# RMP_MACRO_MODULE.net
KiCad netlist of a schematic drawn in Altium Designer
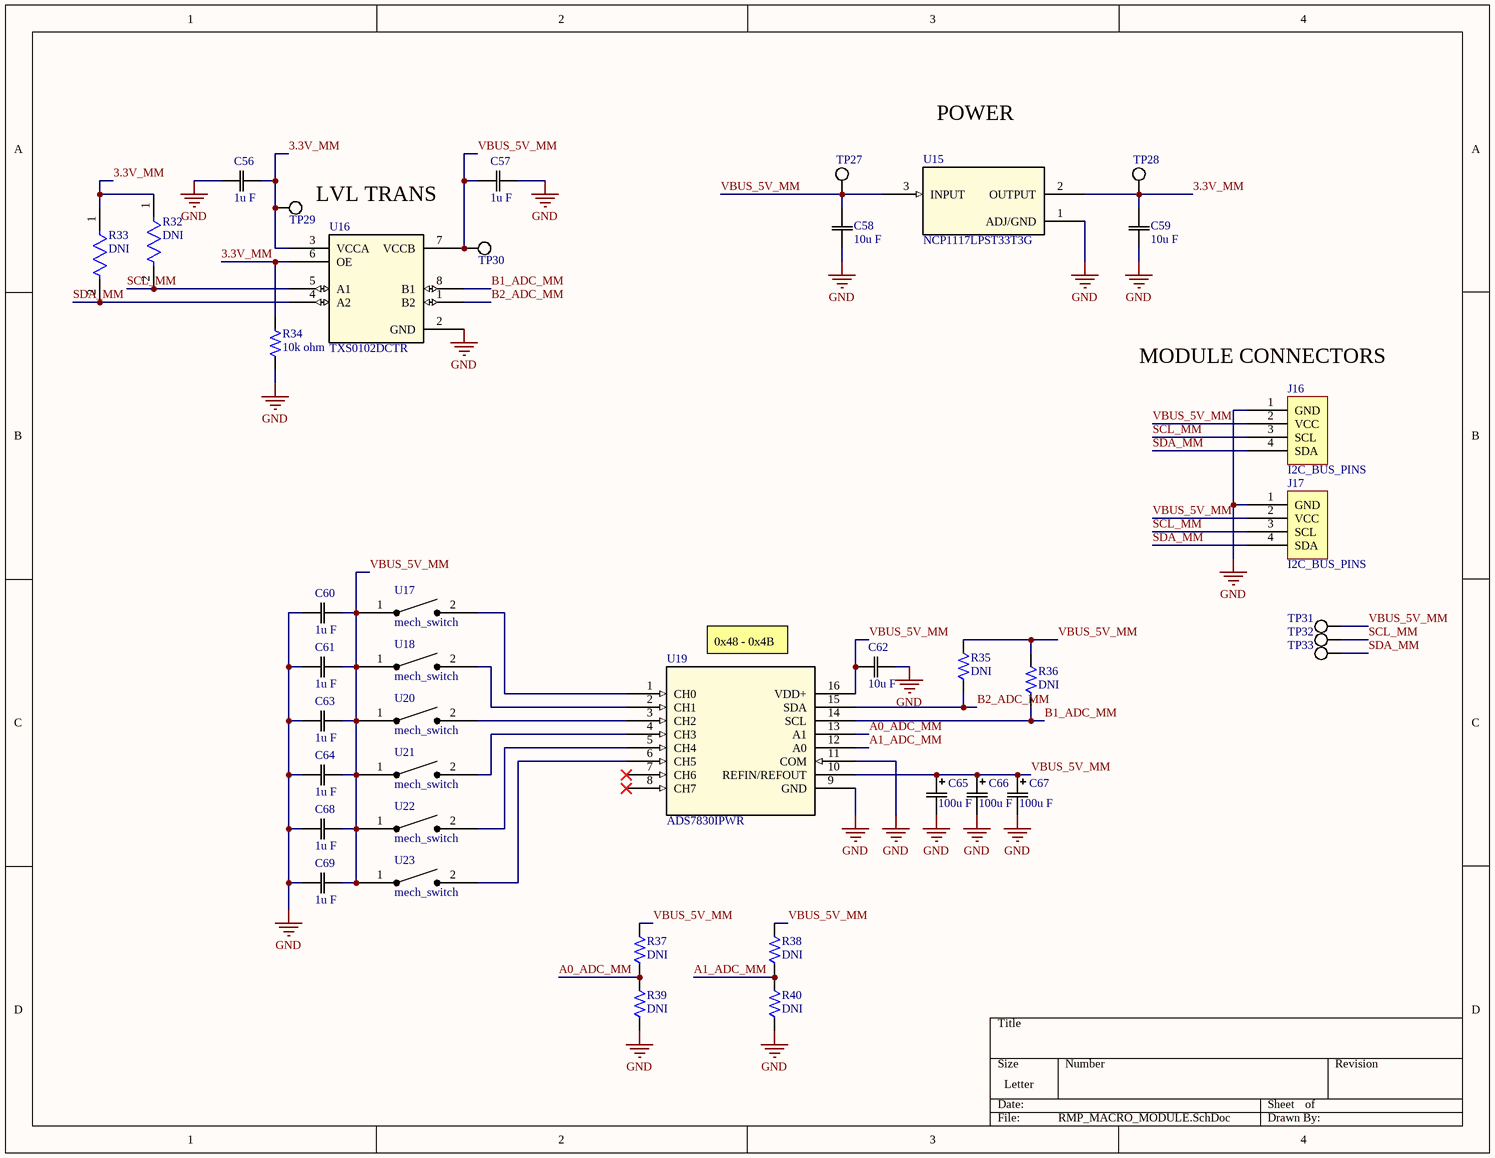
[diagram p0: RMP_MACRO_MODULE.SchDoc]

(export (version "E")
  (design (tool "Eeschema 10.0.6"))
  (components
    (comp (ref "C56")
      (value "1u F")
      (footprint "CAP_CL21B105KAFNNNE_SAM-M")
      (description "1 µF ±10% 25V Ceramic Capacitor X7R 0805 (2012 Metric)")
      (fields (field (name "Comment") "CL21B105KAFNNNE"))
      (libsource (lib "Schlib1") (part "CAP_CL21B105KAFNNNE"))
    )
    (comp (ref "C57")
      (value "1u F")
      (footprint "CAP_CL21B105KAFNNNE_SAM-M")
      (description "1 µF ±10% 25V Ceramic Capacitor X7R 0805 (2012 Metric)")
      (fields (field (name "Comment") "CL21B105KAFNNNE"))
      (libsource (lib "Schlib1") (part "CAP_CL21B105KAFNNNE"))
    )
    (comp (ref "C58")
      (value "10u F")
      (footprint "G-21_MUR-M")
      (description "10 µF ±10% 16V Ceramic Capacitor X5R 0805 (2012 Metric)")
      (fields (field (name "Comment") "GRM21BR61C106KE15K"))
      (libsource (lib "Schlib1") (part "CAP_GRM21BR61C106KE15K"))
    )
    (comp (ref "C59")
      (value "10u F")
      (footprint "G-21_MUR-M")
      (description "10 µF ±10% 16V Ceramic Capacitor X5R 0805 (2012 Metric)")
      (fields (field (name "Comment") "GRM21BR61C106KE15K"))
      (libsource (lib "Schlib1") (part "CAP_GRM21BR61C106KE15K"))
    )
    (comp (ref "C60")
      (value "1u F")
      (footprint "CAP_CL21B105KAFNNNE_SAM-M")
      (description "1 µF ±10% 25V Ceramic Capacitor X7R 0805 (2012 Metric)")
      (fields (field (name "Comment") "CL21B105KAFNNNE"))
      (libsource (lib "Schlib1") (part "CAP_CL21B105KAFNNNE"))
    )
    (comp (ref "C61")
      (value "1u F")
      (footprint "CAP_CL21B105KAFNNNE_SAM-M")
      (description "1 µF ±10% 25V Ceramic Capacitor X7R 0805 (2012 Metric)")
      (fields (field (name "Comment") "CL21B105KAFNNNE"))
      (libsource (lib "Schlib1") (part "CAP_CL21B105KAFNNNE"))
    )
    (comp (ref "C62")
      (value "10u F")
      (footprint "G-21_MUR-M")
      (description "10 µF ±10% 16V Ceramic Capacitor X5R 0805 (2012 Metric)")
      (fields (field (name "Comment") "GRM21BR61C106KE15K"))
      (libsource (lib "Schlib1") (part "CAP_GRM21BR61C106KE15K"))
    )
    (comp (ref "C63")
      (value "1u F")
      (footprint "CAP_CL21B105KAFNNNE_SAM-M")
      (description "1 µF ±10% 25V Ceramic Capacitor X7R 0805 (2012 Metric)")
      (fields (field (name "Comment") "CL21B105KAFNNNE"))
      (libsource (lib "Schlib1") (part "CAP_CL21B105KAFNNNE"))
    )
    (comp (ref "C64")
      (value "1u F")
      (footprint "CAP_CL21B105KAFNNNE_SAM-M")
      (description "1 µF ±10% 25V Ceramic Capacitor X7R 0805 (2012 Metric)")
      (fields (field (name "Comment") "CL21B105KAFNNNE"))
      (libsource (lib "Schlib1") (part "CAP_CL21B105KAFNNNE"))
    )
    (comp (ref "C65")
      (value "100u F")
      (footprint "CAP_YX_6P3X11_RUB")
      (description "CAP ALUM 100UF 20% 35V RADIAL TH")
      (fields (field (name "Comment") "35YXJ100M6.3X11"))
      (libsource (lib "Schlib1") (part "CAP_35YXJ100M6.3X11"))
    )
    (comp (ref "C66")
      (value "100u F")
      (footprint "CAP_YX_6P3X11_RUB")
      (description "CAP ALUM 100UF 20% 35V RADIAL TH")
      (fields (field (name "Comment") "35YXJ100M6.3X11"))
      (libsource (lib "Schlib1") (part "CAP_35YXJ100M6.3X11"))
    )
    (comp (ref "C67")
      (value "100u F")
      (footprint "CAP_YX_6P3X11_RUB")
      (description "CAP ALUM 100UF 20% 35V RADIAL TH")
      (fields (field (name "Comment") "35YXJ100M6.3X11"))
      (libsource (lib "Schlib1") (part "CAP_35YXJ100M6.3X11"))
    )
    (comp (ref "C68")
      (value "1u F")
      (footprint "CAP_CL21B105KAFNNNE_SAM-M")
      (description "1 µF ±10% 25V Ceramic Capacitor X7R 0805 (2012 Metric)")
      (fields (field (name "Comment") "CL21B105KAFNNNE"))
      (libsource (lib "Schlib1") (part "CAP_CL21B105KAFNNNE"))
    )
    (comp (ref "C69")
      (value "1u F")
      (footprint "CAP_CL21B105KAFNNNE_SAM-M")
      (description "1 µF ±10% 25V Ceramic Capacitor X7R 0805 (2012 Metric)")
      (fields (field (name "Comment") "CL21B105KAFNNNE"))
      (libsource (lib "Schlib1") (part "CAP_CL21B105KAFNNNE"))
    )
    (comp (ref "J16")
      (value "I2C_BUS_PINS")
      (footprint "4 PIN HEADER")
      (libsource (lib "Schlib1") (part "I2C_BUS_PINS"))
    )
    (comp (ref "J17")
      (value "I2C_BUS_PINS")
      (footprint "4 PIN HEADER")
      (libsource (lib "Schlib1") (part "I2C_BUS_PINS"))
    )
    (comp (ref "R32")
      (value "RT0805FRE134K7L")
      (footprint "FP-RT0805-MFG")
      (description "RT0805 4.7KΩ 0.125W 50 ppm/°C 0.01%")
      (fields
        (field (name "RESISTANCE") "DNI")
        (field (name "TOLERANCE") "0.0001")
        (field (name "MANUFACTURER") "Yageo")
      )
      (libsource (lib "Altium Content Vault") (part "1029c3af85768c4190bb7ad29bc67b5"))
    )
    (comp (ref "R33")
      (value "RT0805FRE134K7L")
      (footprint "FP-RT0805-MFG")
      (description "RT0805 4.7KΩ 0.125W 50 ppm/°C 0.01%")
      (fields
        (field (name "RESISTANCE") "DNI")
        (field (name "TOLERANCE") "0.0001")
        (field (name "MANUFACTURER") "Yageo")
      )
      (libsource (lib "Altium Content Vault") (part "1029c3af85768c4190bb7ad29bc67b5"))
    )
    (comp (ref "R34")
      (value "10k ohm")
      (footprint "STA_RNCP0805_STP-M")
      (description "10 kOhms ±1% 0.25W, 1/4W Chip Resistor 0805 (2012 Metric) Anti-Sulfur Thin Film")
      (fields (field (name "Comment") "RNCP0805FTD10K0"))
      (libsource (lib "Schlib1") (part "RES_RNCP0805FTD10K0"))
    )
    (comp (ref "R35")
      (value "DNI")
      (footprint "STA_RNCP0805_STP-M")
      (description "10 kOhms ±1% 0.25W, 1/4W Chip Resistor 0805 (2012 Metric) Anti-Sulfur Thin Film")
      (fields (field (name "Comment") "RNCP0805FTD10K0"))
      (libsource (lib "Schlib1") (part "RES_RNCP0805FTD10K0"))
    )
    (comp (ref "R36")
      (value "DNI")
      (footprint "STA_RNCP0805_STP-M")
      (description "10 kOhms ±1% 0.25W, 1/4W Chip Resistor 0805 (2012 Metric) Anti-Sulfur Thin Film")
      (fields (field (name "Comment") "RNCP0805FTD10K0"))
      (libsource (lib "Schlib1") (part "RES_RNCP0805FTD10K0"))
    )
    (comp (ref "R37")
      (value "DNI")
      (footprint "STA_RNCP0805_STP-M")
      (description "10 kOhms ±1% 0.25W, 1/4W Chip Resistor 0805 (2012 Metric) Anti-Sulfur Thin Film")
      (fields (field (name "Comment") "RNCP0805FTD10K0"))
      (libsource (lib "Schlib1") (part "RES_RNCP0805FTD10K0"))
    )
    (comp (ref "R38")
      (value "DNI")
      (footprint "STA_RNCP0805_STP-M")
      (description "10 kOhms ±1% 0.25W, 1/4W Chip Resistor 0805 (2012 Metric) Anti-Sulfur Thin Film")
      (fields (field (name "Comment") "RNCP0805FTD10K0"))
      (libsource (lib "Schlib1") (part "RES_RNCP0805FTD10K0"))
    )
    (comp (ref "R39")
      (value "DNI")
      (footprint "STA_RNCP0805_STP-M")
      (description "10 kOhms ±1% 0.25W, 1/4W Chip Resistor 0805 (2012 Metric) Anti-Sulfur Thin Film")
      (fields (field (name "Comment") "RNCP0805FTD10K0"))
      (libsource (lib "Schlib1") (part "RES_RNCP0805FTD10K0"))
    )
    (comp (ref "R40")
      (value "DNI")
      (footprint "STA_RNCP0805_STP-M")
      (description "10 kOhms ±1% 0.25W, 1/4W Chip Resistor 0805 (2012 Metric) Anti-Sulfur Thin Film")
      (fields (field (name "Comment") "RNCP0805FTD10K0"))
      (libsource (lib "Schlib1") (part "RES_RNCP0805FTD10K0"))
    )
    (comp (ref "TP27")
      (value "TestPoint")
      (footprint "Testpoint")
      (libsource (lib "Schlib1") (part "TestPoint"))
    )
    (comp (ref "TP28")
      (value "TestPoint")
      (footprint "Testpoint")
      (libsource (lib "Schlib1") (part "TestPoint"))
    )
    (comp (ref "TP29")
      (value "TestPoint")
      (footprint "Testpoint")
      (libsource (lib "Schlib1") (part "TestPoint"))
    )
    (comp (ref "TP30")
      (value "TestPoint")
      (footprint "Testpoint")
      (libsource (lib "Schlib1") (part "TestPoint"))
    )
    (comp (ref "TP31")
      (value "TestPoint")
      (footprint "Testpoint")
      (libsource (lib "Schlib1") (part "TestPoint"))
    )
    (comp (ref "TP32")
      (value "TestPoint")
      (footprint "Testpoint")
      (libsource (lib "Schlib1") (part "TestPoint"))
    )
    (comp (ref "TP33")
      (value "TestPoint")
      (footprint "Testpoint")
      (libsource (lib "Schlib1") (part "TestPoint"))
    )
    (comp (ref "U15")
      (value "NCP1117LPST33T3G")
      (footprint "SOT223-3_ONS-M")
      (description "Linear Voltage Regulator IC Positive Fixed 1 Output 1A SOT-223")
      (libsource (lib "Schlib1") (part "NCP1117LPST33T3G"))
    )
    (comp (ref "U16")
      (value "TXS0102DCTR")
      (footprint "DCT8")
      (description "Voltage Level Translator Bidirectional 1 Circuit 2 Channel 24Mbps SM8")
      (libsource (lib "Schlib1") (part "TXS0102DCTR"))
    )
    (comp (ref "U17")
      (value "mech_switch")
      (footprint "SW_MX1A-E1NW_CHY")
      (description "mechanical switch")
      (libsource (lib "Schlib1") (part "mech_switch"))
    )
    (comp (ref "U18")
      (value "mech_switch")
      (footprint "SW_MX1A-E1NW_CHY")
      (description "mechanical switch")
      (libsource (lib "Schlib1") (part "mech_switch"))
    )
    (comp (ref "U19")
      (value "ADS7830IPWR")
      (footprint "PW16-M")
      (description "8 Bit Analog to Digital Converter 4, 8 Input 1 SAR 16-TSSOP")
      (libsource (lib "Schlib1") (part "ADS7830IPWR"))
    )
    (comp (ref "U20")
      (value "mech_switch")
      (footprint "SW_MX1A-E1NW_CHY")
      (description "mechanical switch")
      (libsource (lib "Schlib1") (part "mech_switch"))
    )
    (comp (ref "U21")
      (value "mech_switch")
      (footprint "SW_MX1A-E1NW_CHY")
      (description "mechanical switch")
      (libsource (lib "Schlib1") (part "mech_switch"))
    )
    (comp (ref "U22")
      (value "mech_switch")
      (footprint "SW_MX1A-E1NW_CHY")
      (description "mechanical switch")
      (libsource (lib "Schlib1") (part "mech_switch"))
    )
    (comp (ref "U23")
      (value "mech_switch")
      (footprint "SW_MX1A-E1NW_CHY")
      (description "mechanical switch")
      (libsource (lib "Schlib1") (part "mech_switch"))
    )
  )
  (nets
    (net (code "1") (name "/3.3V_MM") (class "Default")
      (node (ref "C56") (pin "1") (pinfunction "1_1") (pintype "passive"))
      (node (ref "C59") (pin "2") (pinfunction "2_2") (pintype "passive"))
      (node (ref "R32") (pin "1") (pinfunction "1_1") (pintype "passive"))
      (node (ref "R33") (pin "1") (pinfunction "1_1") (pintype "passive"))
      (node (ref "R34") (pin "1") (pinfunction "1_1") (pintype "passive"))
      (node (ref "TP28") (pin "1") (pinfunction "1_1") (pintype "passive"))
      (node (ref "TP29") (pin "1") (pinfunction "1_1") (pintype "passive"))
      (node (ref "U15") (pin "2") (pinfunction "OUTPUT_2") (pintype "power_in"))
      (node (ref "U16") (pin "3") (pinfunction "VCCA_3") (pintype "power_in"))
      (node (ref "U16") (pin "6") (pinfunction "OE_6") (pintype "power_in"))
    )
    (net (code "2") (name "/A0_ADC_MM") (class "Default")
      (node (ref "R37") (pin "1") (pinfunction "1_1") (pintype "passive"))
      (node (ref "R39") (pin "2") (pinfunction "2_2") (pintype "passive"))
      (node (ref "U19") (pin "13") (pinfunction "A1_13") (pintype "passive"))
    )
    (net (code "3") (name "/A1_ADC_MM") (class "Default")
      (node (ref "R38") (pin "1") (pinfunction "1_1") (pintype "passive"))
      (node (ref "R40") (pin "2") (pinfunction "2_2") (pintype "passive"))
      (node (ref "U19") (pin "12") (pinfunction "A0_12") (pintype "passive"))
    )
    (net (code "4") (name "/B1_ADC_MM") (class "Default")
      (node (ref "R36") (pin "1") (pinfunction "1_1") (pintype "passive"))
      (node (ref "U16") (pin "8") (pinfunction "B1_8") (pintype "bidirectional"))
      (node (ref "U19") (pin "14") (pinfunction "SCL_14") (pintype "passive"))
    )
    (net (code "5") (name "/B2_ADC_MM") (class "Default")
      (node (ref "R35") (pin "1") (pinfunction "1_1") (pintype "passive"))
      (node (ref "U16") (pin "1") (pinfunction "B2_1") (pintype "bidirectional"))
      (node (ref "U19") (pin "15") (pinfunction "SDA_15") (pintype "passive"))
    )
    (net (code "6") (name "/SCL_MM") (class "Default")
      (node (ref "J16") (pin "3") (pinfunction "SCL_3") (pintype "passive"))
      (node (ref "J17") (pin "3") (pinfunction "SCL_3") (pintype "passive"))
      (node (ref "R32") (pin "2") (pinfunction "2_2") (pintype "passive"))
      (node (ref "TP32") (pin "1") (pinfunction "1_1") (pintype "passive"))
      (node (ref "U16") (pin "5") (pinfunction "A1_5") (pintype "bidirectional"))
    )
    (net (code "7") (name "/SDA_MM") (class "Default")
      (node (ref "J16") (pin "4") (pinfunction "SDA_4") (pintype "passive"))
      (node (ref "J17") (pin "4") (pinfunction "SDA_4") (pintype "passive"))
      (node (ref "R33") (pin "2") (pinfunction "2_2") (pintype "passive"))
      (node (ref "TP33") (pin "1") (pinfunction "1_1") (pintype "passive"))
      (node (ref "U16") (pin "4") (pinfunction "A2_4") (pintype "bidirectional"))
    )
    (net (code "8") (name "/VBUS_5V_MM") (class "Default")
      (node (ref "C57") (pin "2") (pinfunction "2_2") (pintype "passive"))
      (node (ref "C58") (pin "2") (pinfunction "2_2") (pintype "passive"))
      (node (ref "C60") (pin "1") (pinfunction "1_1") (pintype "passive"))
      (node (ref "C61") (pin "1") (pinfunction "1_1") (pintype "passive"))
      (node (ref "C62") (pin "2") (pinfunction "2_2") (pintype "passive"))
      (node (ref "C63") (pin "1") (pinfunction "1_1") (pintype "passive"))
      (node (ref "C64") (pin "1") (pinfunction "1_1") (pintype "passive"))
      (node (ref "C65") (pin "1") (pinfunction "1_1") (pintype "passive"))
      (node (ref "C66") (pin "1") (pinfunction "1_1") (pintype "passive"))
      (node (ref "C67") (pin "1") (pinfunction "1_1") (pintype "passive"))
      (node (ref "C68") (pin "1") (pinfunction "1_1") (pintype "passive"))
      (node (ref "C69") (pin "1") (pinfunction "1_1") (pintype "passive"))
      (node (ref "J16") (pin "2") (pinfunction "VCC_2") (pintype "passive"))
      (node (ref "J17") (pin "2") (pinfunction "VCC_2") (pintype "passive"))
      (node (ref "R35") (pin "2") (pinfunction "2_2") (pintype "passive"))
      (node (ref "R36") (pin "2") (pinfunction "2_2") (pintype "passive"))
      (node (ref "R37") (pin "2") (pinfunction "2_2") (pintype "passive"))
      (node (ref "R38") (pin "2") (pinfunction "2_2") (pintype "passive"))
      (node (ref "TP27") (pin "1") (pinfunction "1_1") (pintype "passive"))
      (node (ref "TP30") (pin "1") (pinfunction "1_1") (pintype "passive"))
      (node (ref "TP31") (pin "1") (pinfunction "1_1") (pintype "passive"))
      (node (ref "U15") (pin "3") (pinfunction "INPUT_3") (pintype "input"))
      (node (ref "U16") (pin "7") (pinfunction "VCCB_7") (pintype "power_in"))
      (node (ref "U17") (pin "1") (pinfunction "1_1") (pintype "passive"))
      (node (ref "U18") (pin "1") (pinfunction "1_1") (pintype "passive"))
      (node (ref "U19") (pin "10") (pinfunction "REFIN/REFOUT_10") (pintype "power_in"))
      (node (ref "U19") (pin "16") (pinfunction "VDD+_16") (pintype "power_in"))
      (node (ref "U20") (pin "1") (pinfunction "1_1") (pintype "passive"))
      (node (ref "U21") (pin "1") (pinfunction "1_1") (pintype "passive"))
      (node (ref "U22") (pin "1") (pinfunction "1_1") (pintype "passive"))
      (node (ref "U23") (pin "1") (pinfunction "1_1") (pintype "passive"))
    )
    (net (code "9") (name "GND") (class "Default")
      (node (ref "C56") (pin "2") (pinfunction "2_2") (pintype "passive"))
      (node (ref "C57") (pin "1") (pinfunction "1_1") (pintype "passive"))
      (node (ref "C58") (pin "1") (pinfunction "1_1") (pintype "passive"))
      (node (ref "C59") (pin "1") (pinfunction "1_1") (pintype "passive"))
      (node (ref "C60") (pin "2") (pinfunction "2_2") (pintype "passive"))
      (node (ref "C61") (pin "2") (pinfunction "2_2") (pintype "passive"))
      (node (ref "C62") (pin "1") (pinfunction "1_1") (pintype "passive"))
      (node (ref "C63") (pin "2") (pinfunction "2_2") (pintype "passive"))
      (node (ref "C64") (pin "2") (pinfunction "2_2") (pintype "passive"))
      (node (ref "C65") (pin "2") (pinfunction "2_2") (pintype "passive"))
      (node (ref "C66") (pin "2") (pinfunction "2_2") (pintype "passive"))
      (node (ref "C67") (pin "2") (pinfunction "2_2") (pintype "passive"))
      (node (ref "C68") (pin "2") (pinfunction "2_2") (pintype "passive"))
      (node (ref "C69") (pin "2") (pinfunction "2_2") (pintype "passive"))
      (node (ref "J16") (pin "1") (pinfunction "GND_1") (pintype "passive"))
      (node (ref "J17") (pin "1") (pinfunction "GND_1") (pintype "passive"))
      (node (ref "R34") (pin "2") (pinfunction "2_2") (pintype "passive"))
      (node (ref "R39") (pin "1") (pinfunction "1_1") (pintype "passive"))
      (node (ref "R40") (pin "1") (pinfunction "1_1") (pintype "passive"))
      (node (ref "U15") (pin "1") (pinfunction "ADJ/GND_1") (pintype "power_in"))
      (node (ref "U16") (pin "2") (pinfunction "GND_2") (pintype "power_in"))
      (node (ref "U19") (pin "11") (pinfunction "COM_11") (pintype "input"))
      (node (ref "U19") (pin "9") (pinfunction "GND_9") (pintype "power_in"))
    )
    (net (code "10") (name "Net-(U19-CH0)") (class "Default")
      (node (ref "U17") (pin "2") (pinfunction "2_2") (pintype "passive"))
      (node (ref "U19") (pin "1") (pinfunction "CH0_1") (pintype "input"))
    )
    (net (code "11") (name "Net-(U19-CH1)") (class "Default")
      (node (ref "U18") (pin "2") (pinfunction "2_2") (pintype "passive"))
      (node (ref "U19") (pin "2") (pinfunction "CH1_2") (pintype "input"))
    )
    (net (code "12") (name "Net-(U19-CH2)") (class "Default")
      (node (ref "U19") (pin "3") (pinfunction "CH2_3") (pintype "input"))
      (node (ref "U20") (pin "2") (pinfunction "2_2") (pintype "passive"))
    )
    (net (code "13") (name "Net-(U19-CH3)") (class "Default")
      (node (ref "U19") (pin "4") (pinfunction "CH3_4") (pintype "input"))
      (node (ref "U21") (pin "2") (pinfunction "2_2") (pintype "passive"))
    )
    (net (code "14") (name "Net-(U19-CH4)") (class "Default")
      (node (ref "U19") (pin "5") (pinfunction "CH4_5") (pintype "input"))
      (node (ref "U22") (pin "2") (pinfunction "2_2") (pintype "passive"))
    )
    (net (code "15") (name "Net-(U19-CH5)") (class "Default")
      (node (ref "U19") (pin "6") (pinfunction "CH5_6") (pintype "input"))
      (node (ref "U23") (pin "2") (pinfunction "2_2") (pintype "passive"))
    )
    (net (code "16") (name "unconnected-(U19-CH6-Pad7)") (class "Default")
      (node (ref "U19") (pin "7") (pinfunction "CH6_7") (pintype "input+no_connect"))
    )
    (net (code "17") (name "unconnected-(U19-CH7-Pad8)") (class "Default")
      (node (ref "U19") (pin "8") (pinfunction "CH7_8") (pintype "input+no_connect"))
    )
  )
)
